# 4OUTmcp4628_PANEL.net
KiCad netlist of a schematic drawn in EAGLE
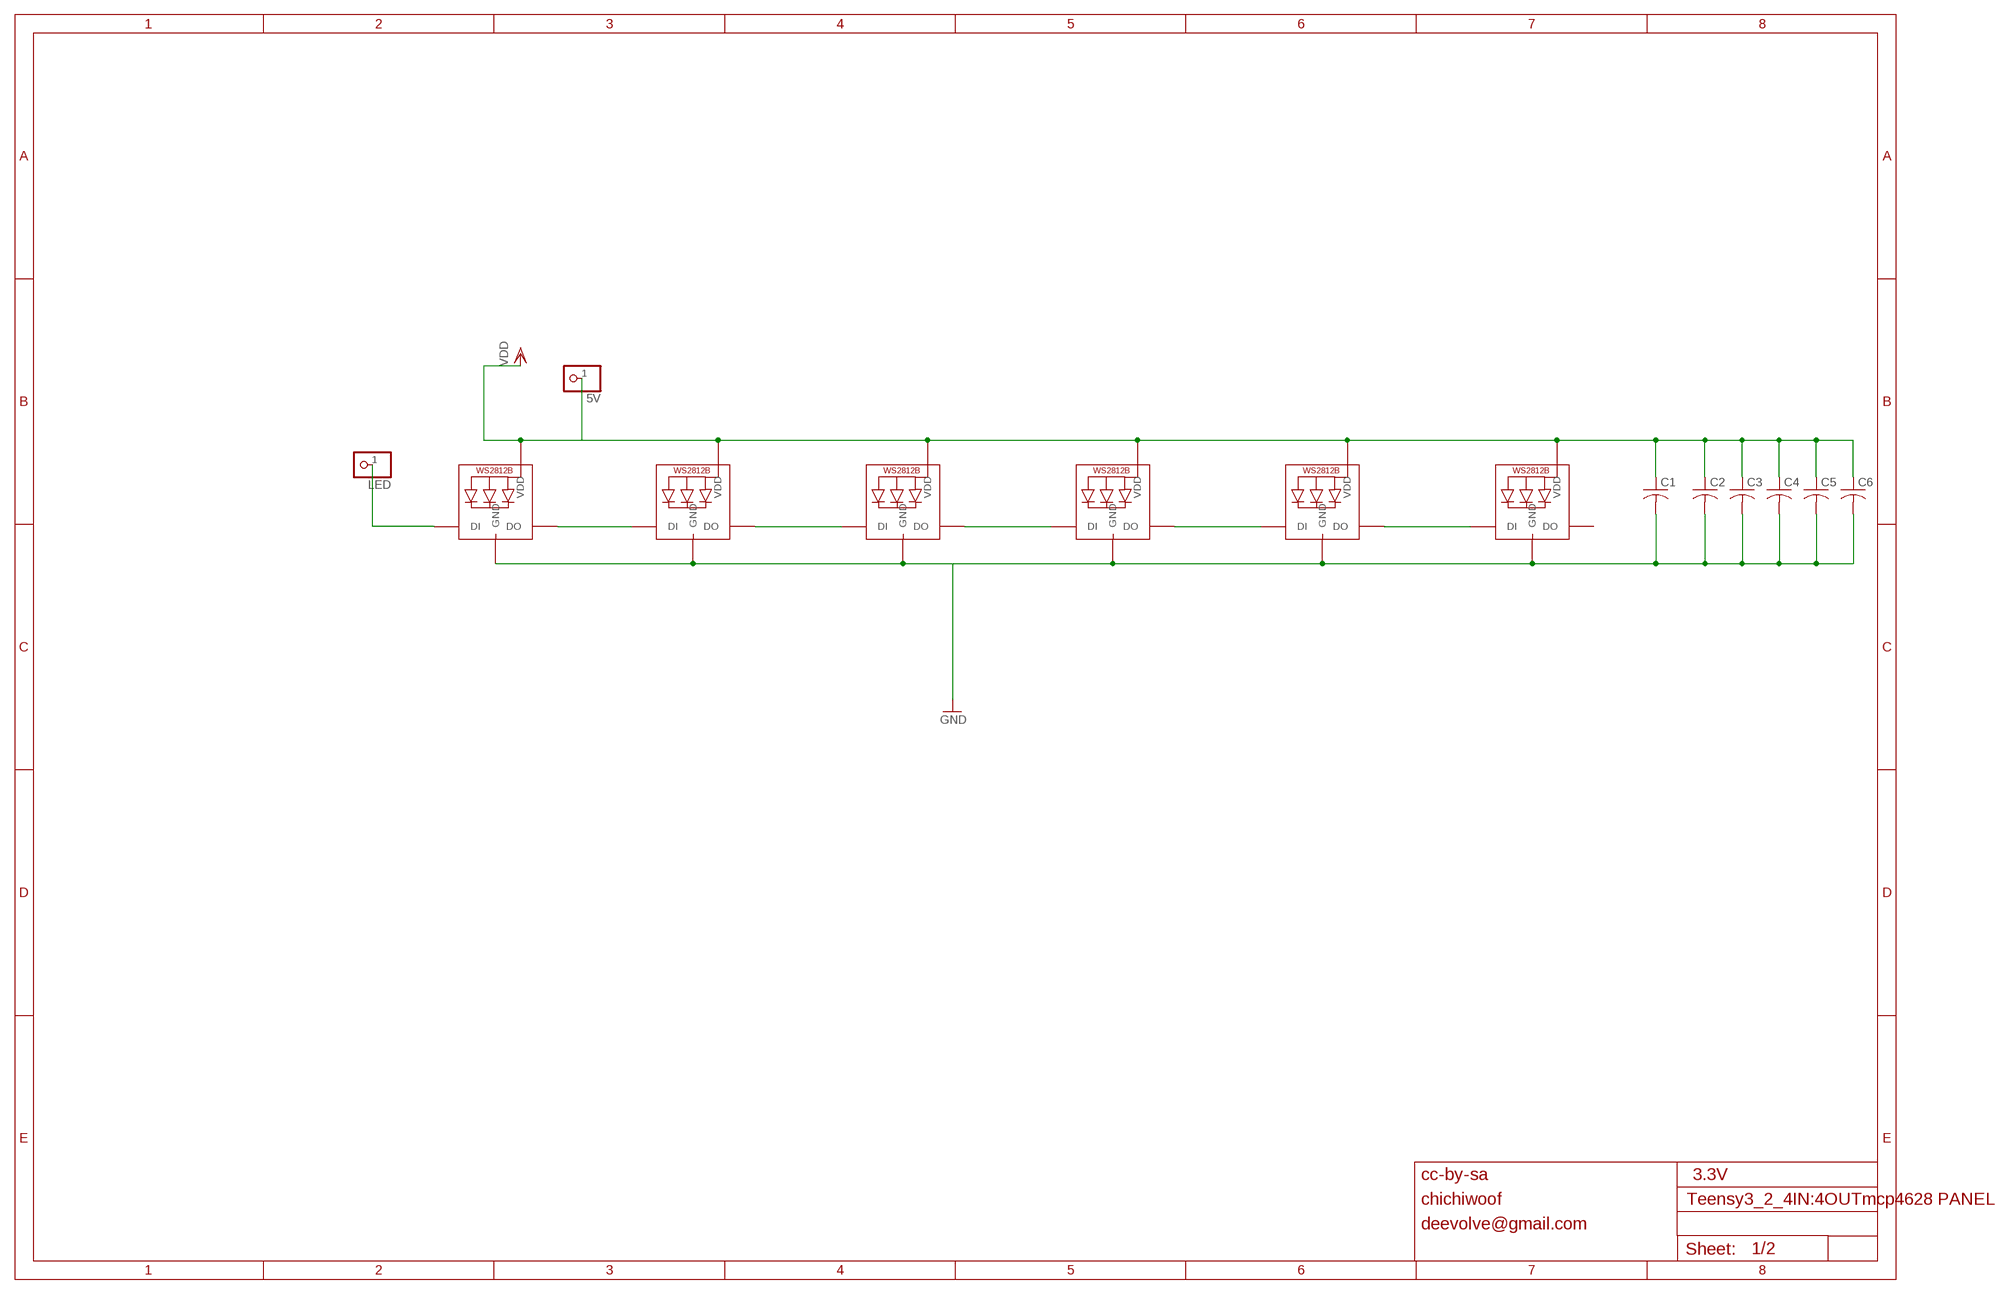
[diagram p0: schematic, sheet 1]
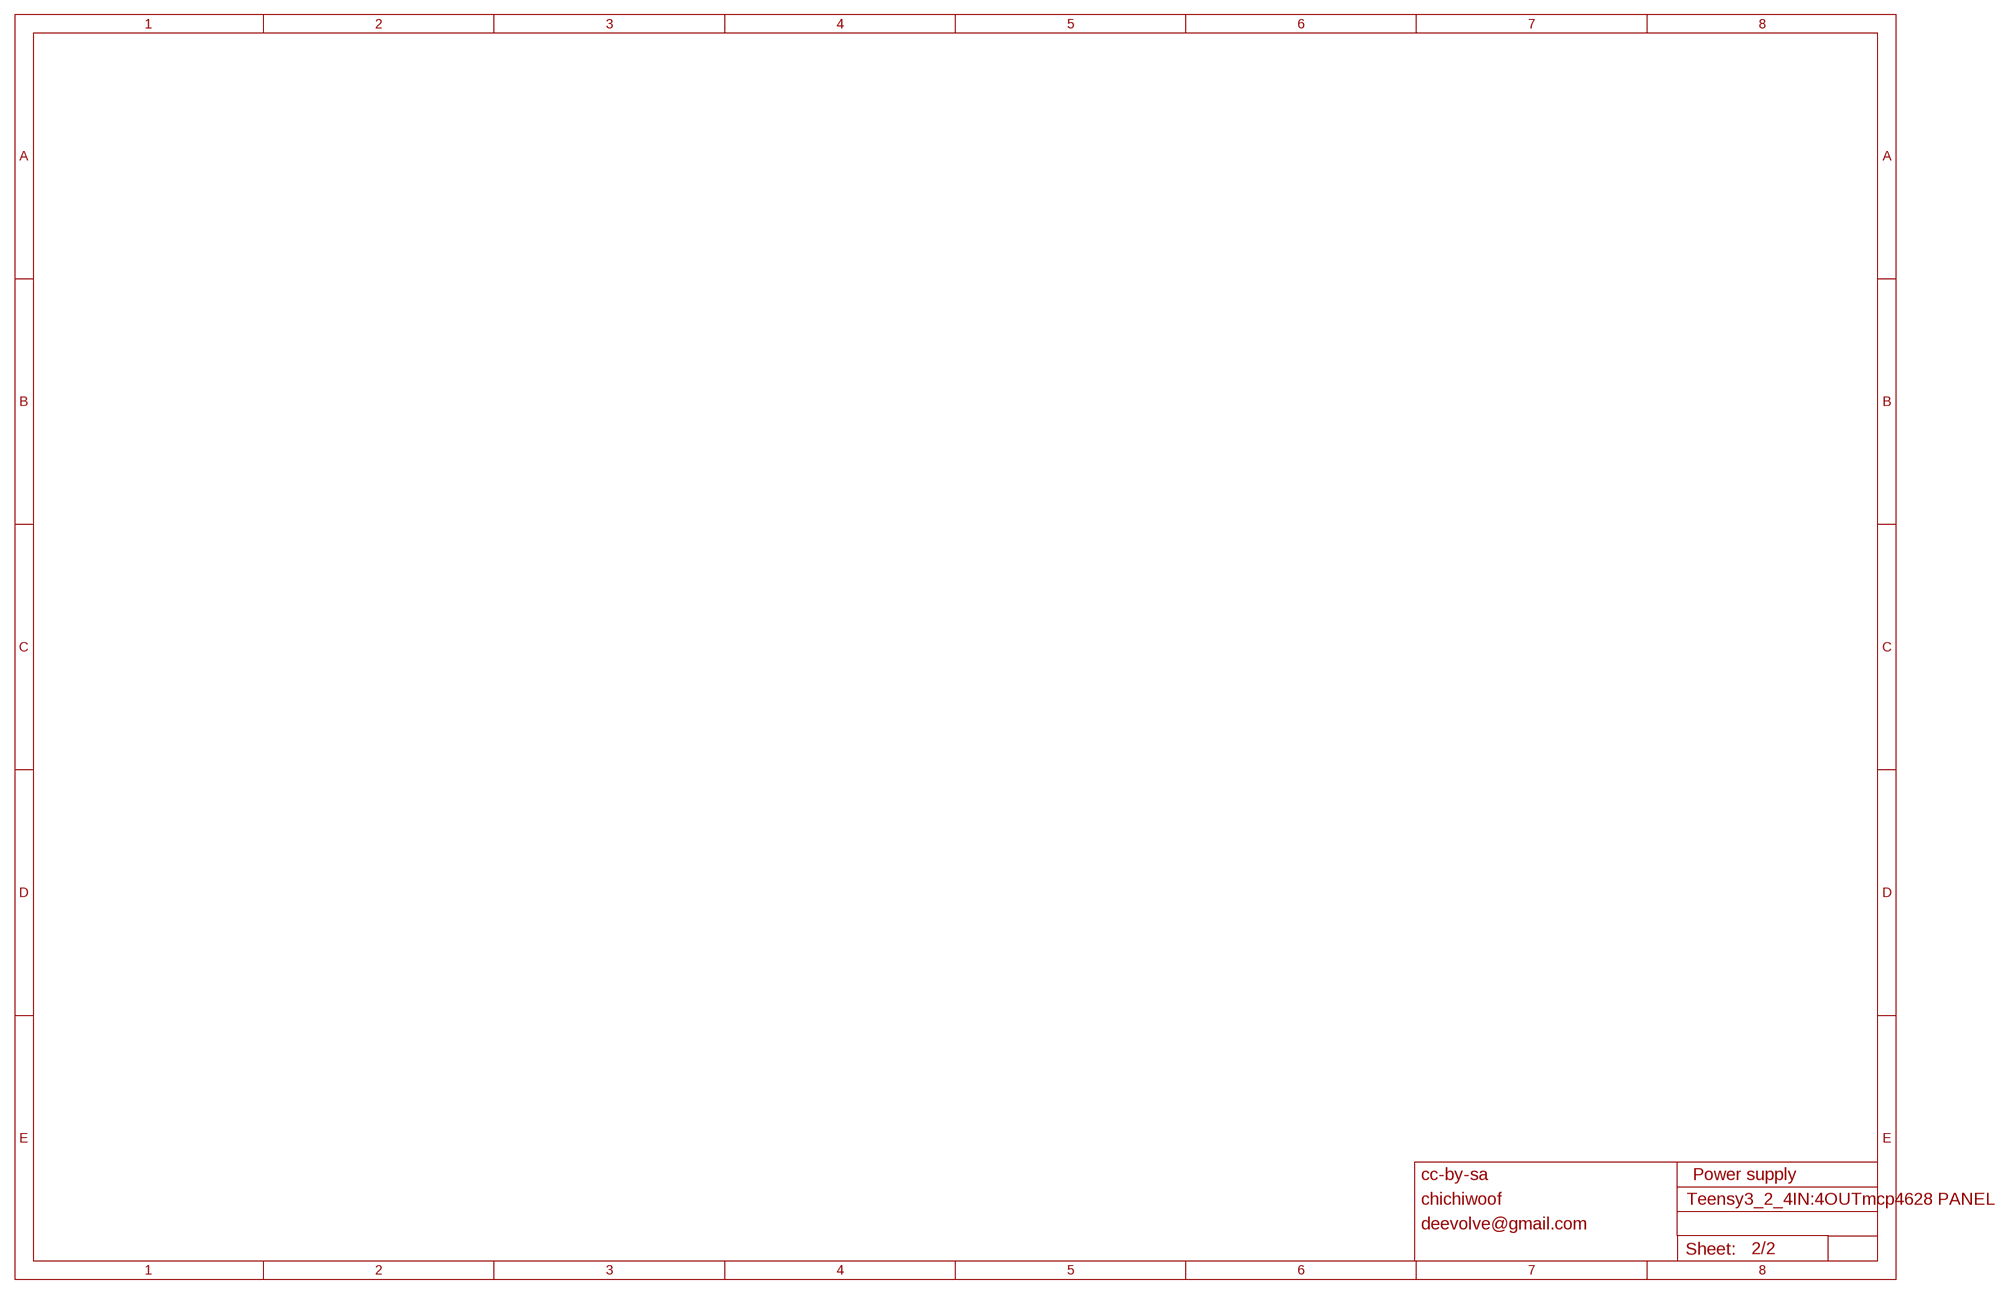
[diagram p1: schematic, sheet 2]

(export (version "E")
  (design (tool "Eeschema 10.0.6"))
  (components
    (comp (ref "5V")
      (value "NEOPIXELRING_PINHD-1X1CB")
      (footprint "eagle-import:NEOPIXELRING_1X01-CLEANBIG")
      (libsource (lib "eagle-import") (part "NEOPIXELRING_PINHD-1X1CB"))
    )
    (comp (ref "C1")
      (value "C-USC0603")
      (footprint "eagle-import:C0603")
      (libsource (lib "eagle-import") (part "C-USC0603"))
    )
    (comp (ref "C2")
      (value "C-USC0603")
      (footprint "eagle-import:C0603")
      (libsource (lib "eagle-import") (part "C-USC0603"))
    )
    (comp (ref "C3")
      (value "C-USC0603")
      (footprint "eagle-import:C0603")
      (libsource (lib "eagle-import") (part "C-USC0603"))
    )
    (comp (ref "C4")
      (value "C-USC0603")
      (footprint "eagle-import:C0603")
      (libsource (lib "eagle-import") (part "C-USC0603"))
    )
    (comp (ref "C5")
      (value "C-USC0603")
      (footprint "eagle-import:C0603")
      (libsource (lib "eagle-import") (part "C-USC0603"))
    )
    (comp (ref "C6")
      (value "C-USC0603")
      (footprint "eagle-import:C0603")
      (libsource (lib "eagle-import") (part "C-USC0603"))
    )
    (comp (ref "LED")
      (value "NEOPIXELRING_PINHD-1X1CB")
      (footprint "eagle-import:NEOPIXELRING_1X01-CLEANBIG")
      (libsource (lib "eagle-import") (part "NEOPIXELRING_PINHD-1X1CB"))
    )
    (comp (ref "LED1")
      (value "WS2812B5050")
      (footprint "eagle-import:WS2812B")
      (fields (field (name "MF") "SparkFun Electronics") (field (name "MP") "WS2812B"))
      (libsource (lib "eagle-import") (part "WS2812B5050"))
    )
    (comp (ref "LED2")
      (value "WS2812B5050")
      (footprint "eagle-import:WS2812B")
      (fields (field (name "MF") "SparkFun Electronics") (field (name "MP") "WS2812B"))
      (libsource (lib "eagle-import") (part "WS2812B5050"))
    )
    (comp (ref "LED3")
      (value "WS2812B5050")
      (footprint "eagle-import:WS2812B")
      (fields (field (name "MF") "SparkFun Electronics") (field (name "MP") "WS2812B"))
      (libsource (lib "eagle-import") (part "WS2812B5050"))
    )
    (comp (ref "LED4")
      (value "WS2812B5050")
      (footprint "eagle-import:WS2812B")
      (fields (field (name "MF") "SparkFun Electronics") (field (name "MP") "WS2812B"))
      (libsource (lib "eagle-import") (part "WS2812B5050"))
    )
    (comp (ref "LED5")
      (value "WS2812B5050")
      (footprint "eagle-import:WS2812B")
      (fields (field (name "MF") "SparkFun Electronics") (field (name "MP") "WS2812B"))
      (libsource (lib "eagle-import") (part "WS2812B5050"))
    )
    (comp (ref "LED7")
      (value "WS2812B5050")
      (footprint "eagle-import:WS2812B")
      (fields (field (name "MF") "SparkFun Electronics") (field (name "MP") "WS2812B"))
      (libsource (lib "eagle-import") (part "WS2812B5050"))
    )
  )
  (nets
    (net (code "1") (name "GND") (class "Default")
      (node (ref "C1") (pin "2") (pinfunction "2_2") (pintype "passive"))
      (node (ref "C2") (pin "2") (pinfunction "2_2") (pintype "passive"))
      (node (ref "C3") (pin "2") (pinfunction "2_2") (pintype "passive"))
      (node (ref "C4") (pin "2") (pinfunction "2_2") (pintype "passive"))
      (node (ref "C5") (pin "2") (pinfunction "2_2") (pintype "passive"))
      (node (ref "C6") (pin "2") (pinfunction "2_2") (pintype "passive"))
      (node (ref "LED1") (pin "3-GND") (pinfunction "GND_3-GND") (pintype "power_in"))
      (node (ref "LED2") (pin "3-GND") (pinfunction "GND_3-GND") (pintype "power_in"))
      (node (ref "LED3") (pin "3-GND") (pinfunction "GND_3-GND") (pintype "power_in"))
      (node (ref "LED4") (pin "3-GND") (pinfunction "GND_3-GND") (pintype "power_in"))
      (node (ref "LED5") (pin "3-GND") (pinfunction "GND_3-GND") (pintype "power_in"))
      (node (ref "LED7") (pin "3-GND") (pinfunction "GND_3-GND") (pintype "power_in"))
    )
    (net (code "2") (name "Net-(LED1-DI)") (class "Default")
      (node (ref "LED1") (pin "4-DIN") (pinfunction "DI_4-DIN") (pintype "input"))
      (node (ref "LED7") (pin "2-DOUT") (pinfunction "DO_2-DOUT") (pintype "output"))
    )
    (net (code "3") (name "Net-(LED1-DO)") (class "Default")
      (node (ref "LED1") (pin "2-DOUT") (pinfunction "DO_2-DOUT") (pintype "output"))
      (node (ref "LED2") (pin "4-DIN") (pinfunction "DI_4-DIN") (pintype "input"))
    )
    (net (code "4") (name "Net-(LED2-DO)") (class "Default")
      (node (ref "LED2") (pin "2-DOUT") (pinfunction "DO_2-DOUT") (pintype "output"))
      (node (ref "LED3") (pin "4-DIN") (pinfunction "DI_4-DIN") (pintype "input"))
    )
    (net (code "5") (name "Net-(LED3-DO)") (class "Default")
      (node (ref "LED3") (pin "2-DOUT") (pinfunction "DO_2-DOUT") (pintype "output"))
      (node (ref "LED4") (pin "4-DIN") (pinfunction "DI_4-DIN") (pintype "input"))
    )
    (net (code "6") (name "Net-(LED4-DO)") (class "Default")
      (node (ref "LED4") (pin "2-DOUT") (pinfunction "DO_2-DOUT") (pintype "output"))
      (node (ref "LED5") (pin "4-DIN") (pinfunction "DI_4-DIN") (pintype "input"))
    )
    (net (code "7") (name "Net-(LED7-DI)") (class "Default")
      (node (ref "LED") (pin "1") (pinfunction "1_1") (pintype "passive"))
      (node (ref "LED7") (pin "4-DIN") (pinfunction "DI_4-DIN") (pintype "input"))
    )
    (net (code "8") (name "VDD") (class "Default")
      (node (ref "5V") (pin "1") (pinfunction "1_1") (pintype "passive"))
      (node (ref "C1") (pin "1") (pinfunction "1_1") (pintype "passive"))
      (node (ref "C2") (pin "1") (pinfunction "1_1") (pintype "passive"))
      (node (ref "C3") (pin "1") (pinfunction "1_1") (pintype "passive"))
      (node (ref "C4") (pin "1") (pinfunction "1_1") (pintype "passive"))
      (node (ref "C5") (pin "1") (pinfunction "1_1") (pintype "passive"))
      (node (ref "C6") (pin "1") (pinfunction "1_1") (pintype "passive"))
      (node (ref "LED1") (pin "1-VDD") (pinfunction "VDD_1-VDD") (pintype "power_in"))
      (node (ref "LED2") (pin "1-VDD") (pinfunction "VDD_1-VDD") (pintype "power_in"))
      (node (ref "LED3") (pin "1-VDD") (pinfunction "VDD_1-VDD") (pintype "power_in"))
      (node (ref "LED4") (pin "1-VDD") (pinfunction "VDD_1-VDD") (pintype "power_in"))
      (node (ref "LED5") (pin "1-VDD") (pinfunction "VDD_1-VDD") (pintype "power_in"))
      (node (ref "LED7") (pin "1-VDD") (pinfunction "VDD_1-VDD") (pintype "power_in"))
    )
    (net (code "9") (name "unconnected-(LED5-DO-Pad2-DOUT)") (class "Default")
      (node (ref "LED5") (pin "2-DOUT") (pinfunction "DO_2-DOUT") (pintype "output"))
    )
  )
)
